# pH-meter.net
KiCad netlist of a schematic drawn in Altium Designer
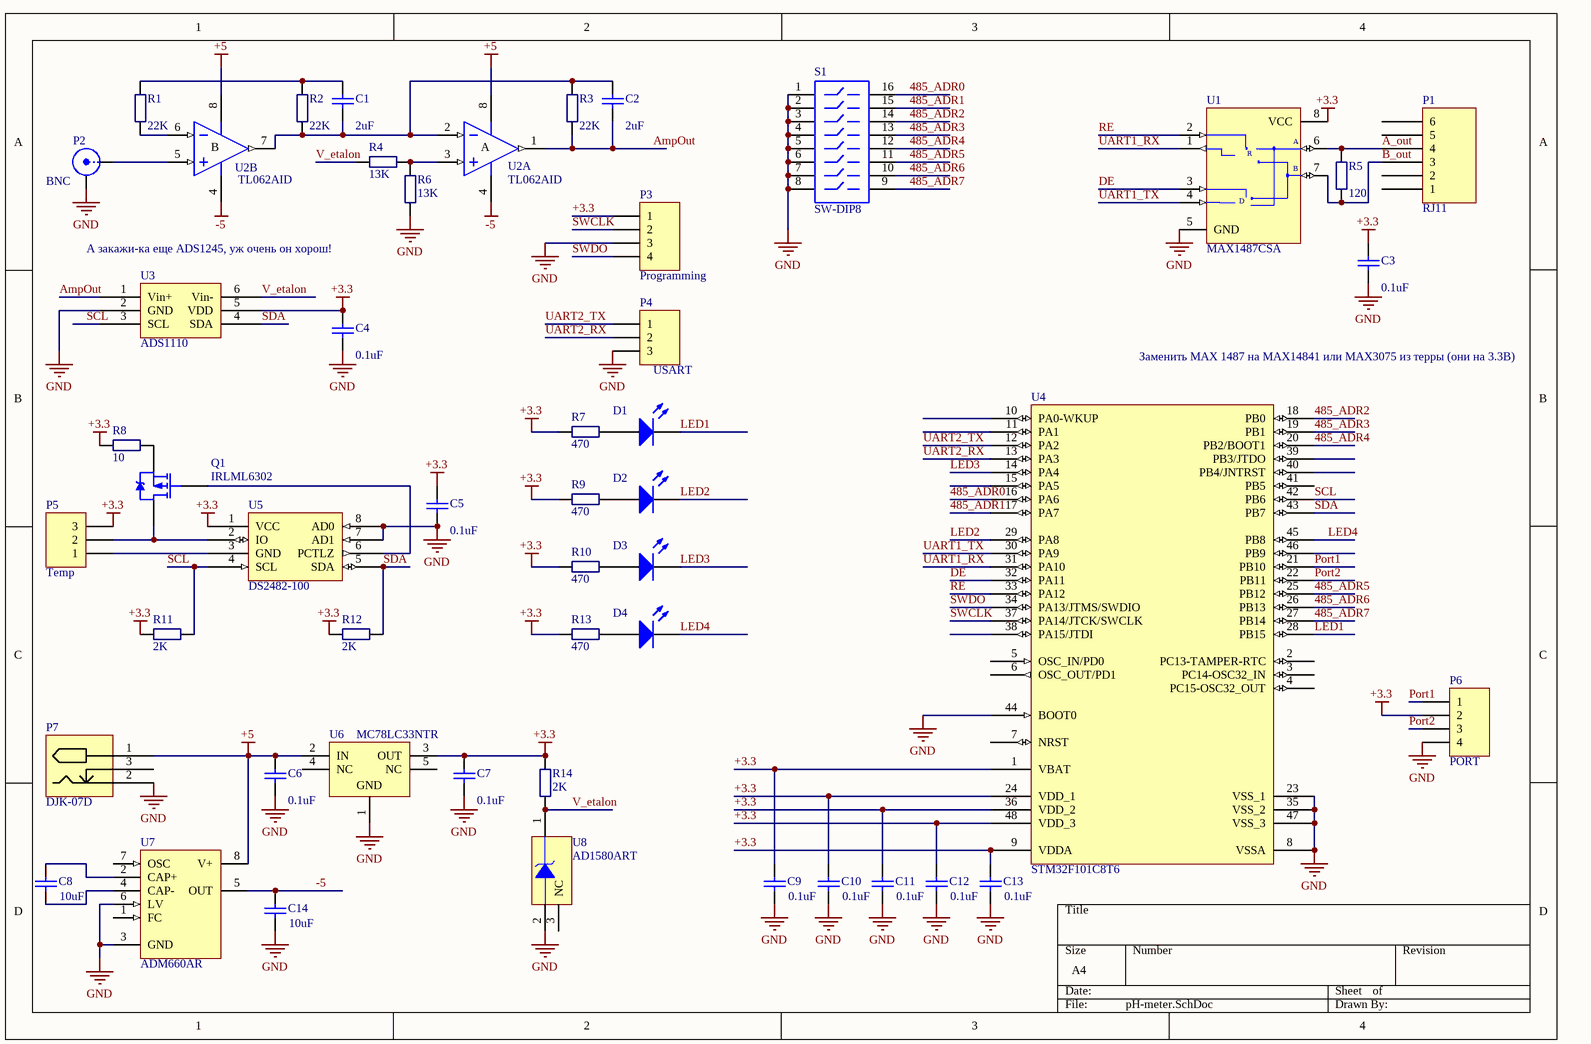
[diagram p0: pH-meter.SchDoc]

(export (version "E")
  (design (tool "Eeschema 10.0.6"))
  (components
    (comp (ref "C1")
      (value "2uF")
      (footprint "1608[0603]")
      (description "Capacitor (Semiconductor SIM Model)")
      (fields (field (name "Comment") "Cap Semi") (field (name "PUBLISHER") "Altium Limited"))
      (libsource (lib "Miscellaneous Devices") (part "Cap Semi"))
    )
    (comp (ref "C2")
      (value "2uF")
      (footprint "1608[0603]")
      (description "Capacitor (Semiconductor SIM Model)")
      (fields (field (name "Comment") "Cap Semi") (field (name "PUBLISHER") "Altium Limited"))
      (libsource (lib "Miscellaneous Devices") (part "Cap Semi"))
    )
    (comp (ref "C3")
      (value "0.1uF")
      (footprint "1608[0603]")
      (description "Capacitor (Semiconductor SIM Model)")
      (fields (field (name "Comment") "Cap Semi") (field (name "PUBLISHER") "Altium Limited"))
      (libsource (lib "Miscellaneous Devices") (part "Cap Semi"))
    )
    (comp (ref "C4")
      (value "0.1uF")
      (footprint "1608[0603]")
      (description "Capacitor (Semiconductor SIM Model)")
      (fields (field (name "Comment") "Cap Semi") (field (name "PUBLISHER") "Altium Limited"))
      (libsource (lib "Miscellaneous Devices") (part "Cap Semi"))
    )
    (comp (ref "C5")
      (value "0.1uF")
      (footprint "1608[0603]")
      (description "Capacitor (Semiconductor SIM Model)")
      (fields (field (name "Comment") "Cap Semi") (field (name "PUBLISHER") "Altium Limited"))
      (libsource (lib "Miscellaneous Devices") (part "Cap Semi"))
    )
    (comp (ref "C6")
      (value "0.1uF")
      (footprint "1608[0603]")
      (description "Capacitor (Semiconductor SIM Model)")
      (fields (field (name "Comment") "Cap Semi") (field (name "PUBLISHER") "Altium Limited"))
      (libsource (lib "Miscellaneous Devices") (part "Cap Semi"))
    )
    (comp (ref "C7")
      (value "0.1uF")
      (footprint "1608[0603]")
      (description "Capacitor (Semiconductor SIM Model)")
      (fields (field (name "Comment") "Cap Semi") (field (name "PUBLISHER") "Altium Limited"))
      (libsource (lib "Miscellaneous Devices") (part "Cap Semi"))
    )
    (comp (ref "C8")
      (value "10uF")
      (footprint "1608[0603]")
      (description "Capacitor (Semiconductor SIM Model)")
      (fields (field (name "Comment") "Cap Semi") (field (name "PUBLISHER") "Altium Limited"))
      (libsource (lib "Miscellaneous Devices") (part "Cap Semi"))
    )
    (comp (ref "C9")
      (value "0.1uF")
      (footprint "1608[0603]")
      (description "Capacitor (Semiconductor SIM Model)")
      (fields (field (name "PUBLISHER") "Altium Limited"))
      (libsource (lib "Miscellaneous Devices") (part "Cap Semi"))
    )
    (comp (ref "C10")
      (value "0.1uF")
      (footprint "1608[0603]")
      (description "Capacitor (Semiconductor SIM Model)")
      (fields (field (name "PUBLISHER") "Altium Limited"))
      (libsource (lib "Miscellaneous Devices") (part "Cap Semi"))
    )
    (comp (ref "C11")
      (value "0.1uF")
      (footprint "1608[0603]")
      (description "Capacitor (Semiconductor SIM Model)")
      (fields (field (name "PUBLISHER") "Altium Limited"))
      (libsource (lib "Miscellaneous Devices") (part "Cap Semi"))
    )
    (comp (ref "C12")
      (value "0.1uF")
      (footprint "1608[0603]")
      (description "Capacitor (Semiconductor SIM Model)")
      (fields (field (name "PUBLISHER") "Altium Limited"))
      (libsource (lib "Miscellaneous Devices") (part "Cap Semi"))
    )
    (comp (ref "C13")
      (value "0.1uF")
      (footprint "1608[0603]")
      (description "Capacitor (Semiconductor SIM Model)")
      (fields (field (name "PUBLISHER") "Altium Limited"))
      (libsource (lib "Miscellaneous Devices") (part "Cap Semi"))
    )
    (comp (ref "C14")
      (value "10uF")
      (footprint "1608[0603]")
      (description "Capacitor (Semiconductor SIM Model)")
      (fields (field (name "Comment") "Cap Semi") (field (name "PUBLISHER") "Altium Limited"))
      (libsource (lib "Miscellaneous Devices") (part "Cap Semi"))
    )
    (comp (ref "D1")
      (value "LED1")
      (footprint "LED-1")
      (description "Typical RED GaAs LED")
      (fields (field (name "PUBLISHER") "Altium Limited"))
      (libsource (lib "Miscellaneous Devices") (part "LED1"))
    )
    (comp (ref "D2")
      (value "LED1")
      (footprint "LED-1")
      (description "Typical RED GaAs LED")
      (fields (field (name "PUBLISHER") "Altium Limited"))
      (libsource (lib "Miscellaneous Devices") (part "LED1"))
    )
    (comp (ref "D3")
      (value "LED1")
      (footprint "LED-1")
      (description "Typical RED GaAs LED")
      (fields (field (name "PUBLISHER") "Altium Limited"))
      (libsource (lib "Miscellaneous Devices") (part "LED1"))
    )
    (comp (ref "D4")
      (value "LED1")
      (footprint "LED-1")
      (description "Typical RED GaAs LED")
      (fields (field (name "PUBLISHER") "Altium Limited"))
      (libsource (lib "Miscellaneous Devices") (part "LED1"))
    )
    (comp (ref "P1")
      (value "RJ11")
      (footprint "RJ11_6")
      (description "RJ11 6pin connector")
      (libsource (lib "MyLib") (part "RJ11_6C"))
    )
    (comp (ref "P2")
      (value "BNC")
      (footprint "BNC_RA CON")
      (description "BNC Elbow Connector")
      (fields (field (name "PUBLISHER") "Altium Limited"))
      (libsource (lib "Miscellaneous Connectors") (part "BNC"))
    )
    (comp (ref "P3")
      (value "Programming")
      (footprint "HDR1X4")
      (description "Header, 4-Pin")
      (fields (field (name "PUBLISHER") "Altium Limited"))
      (libsource (lib "Miscellaneous Connectors") (part "Header 4"))
    )
    (comp (ref "P4")
      (value "USART")
      (footprint "HDR1X3")
      (description "Header, 3-Pin")
      (fields (field (name "PUBLISHER") "Altium Limited"))
      (libsource (lib "Miscellaneous Connectors") (part "Header 3"))
    )
    (comp (ref "P5")
      (value "Temp")
      (footprint "HDR1X3")
      (description "Header, 3-Pin")
      (fields (field (name "PUBLISHER") "Altium Limited"))
      (libsource (lib "") (part "Header 3_1"))
    )
    (comp (ref "P6")
      (value "PORT")
      (footprint "HDR1X4")
      (description "Header, 4-Pin")
      (fields (field (name "PUBLISHER") "Altium Limited"))
      (libsource (lib "Miscellaneous Connectors") (part "Header 4"))
    )
    (comp (ref "P7")
      (value "DJK-07D")
      (footprint "DJK-07D")
      (description "DJK-07D Разъем питани  штырев. 1,3мм (п) на плату")
      (libsource (lib "MyLib") (part "DJK-07D"))
    )
    (comp (ref "Q1")
      (value "IRLML6302")
      (footprint "SOT-23_N")
      (description "HEXFET Power MOSFET")
      (fields (field (name "PUBLISHER") "Altium Limited"))
      (libsource (lib "IR Discrete MOSFET - Power") (part "IRLML6302"))
    )
    (comp (ref "R1")
      (value "22K")
      (footprint "J1-0603")
      (description "Resistor")
      (fields (field (name "Comment") "Res_SMD") (field (name "PUBLISHER") "Altium Limited"))
      (libsource (lib "MyLib") (part "Res_SMD"))
    )
    (comp (ref "R2")
      (value "22K")
      (footprint "J1-0603")
      (description "Resistor")
      (fields (field (name "Comment") "Res_SMD") (field (name "PUBLISHER") "Altium Limited"))
      (libsource (lib "MyLib") (part "Res_SMD"))
    )
    (comp (ref "R3")
      (value "22K")
      (footprint "J1-0603")
      (description "Resistor")
      (fields (field (name "Comment") "Res_SMD") (field (name "PUBLISHER") "Altium Limited"))
      (libsource (lib "MyLib") (part "Res_SMD"))
    )
    (comp (ref "R4")
      (value "13K")
      (footprint "J1-0603")
      (description "Resistor")
      (fields (field (name "Comment") "Res_SMD") (field (name "PUBLISHER") "Altium Limited"))
      (libsource (lib "MyLib") (part "Res_SMD"))
    )
    (comp (ref "R5")
      (value "120")
      (footprint "J1-0603")
      (description "Resistor")
      (fields (field (name "Comment") "Res_SMD") (field (name "PUBLISHER") "Altium Limited"))
      (libsource (lib "MyLib") (part "Res_SMD"))
    )
    (comp (ref "R6")
      (value "13K")
      (footprint "J1-0603")
      (description "Resistor")
      (fields (field (name "Comment") "Res_SMD") (field (name "PUBLISHER") "Altium Limited"))
      (libsource (lib "MyLib") (part "Res_SMD"))
    )
    (comp (ref "R7")
      (value "470")
      (footprint "J1-0603")
      (description "Resistor")
      (fields (field (name "PUBLISHER") "Altium Limited"))
      (libsource (lib "MyLib") (part "Res_SMD"))
    )
    (comp (ref "R8")
      (value "10")
      (footprint "J1-0603")
      (description "Resistor")
      (fields (field (name "Comment") "Res_SMD") (field (name "PUBLISHER") "Altium Limited"))
      (libsource (lib "MyLib") (part "Res_SMD"))
    )
    (comp (ref "R9")
      (value "470")
      (footprint "J1-0603")
      (description "Resistor")
      (fields (field (name "PUBLISHER") "Altium Limited"))
      (libsource (lib "MyLib") (part "Res_SMD"))
    )
    (comp (ref "R10")
      (value "470")
      (footprint "J1-0603")
      (description "Resistor")
      (fields (field (name "PUBLISHER") "Altium Limited"))
      (libsource (lib "MyLib") (part "Res_SMD"))
    )
    (comp (ref "R11")
      (value "2K")
      (footprint "J1-0603")
      (description "Resistor")
      (fields (field (name "Comment") "Res_SMD") (field (name "PUBLISHER") "Altium Limited"))
      (libsource (lib "MyLib") (part "Res_SMD"))
    )
    (comp (ref "R12")
      (value "2K")
      (footprint "J1-0603")
      (description "Resistor")
      (fields (field (name "Comment") "Res_SMD") (field (name "PUBLISHER") "Altium Limited"))
      (libsource (lib "MyLib") (part "Res_SMD"))
    )
    (comp (ref "R13")
      (value "470")
      (footprint "J1-0603")
      (description "Resistor")
      (fields (field (name "PUBLISHER") "Altium Limited"))
      (libsource (lib "MyLib") (part "Res_SMD"))
    )
    (comp (ref "R14")
      (value "2K")
      (footprint "J1-0603")
      (description "Resistor")
      (fields (field (name "Comment") "Res_SMD") (field (name "PUBLISHER") "Altium Limited"))
      (libsource (lib "MyLib") (part "Res_SMD"))
    )
    (comp (ref "S1")
      (value "SW-DIP8")
      (footprint "DIP-16-KEY")
      (description "4009 Series DIP Switch, Raised actuator")
      (fields (field (name "PUBLISHER") "Altium Limited"))
      (libsource (lib "Miscellaneous Devices") (part "SW-DIP8"))
    )
    (comp (ref "U1")
      (value "MAX1487CSA")
      (footprint "NSO8_N")
      (description "Low-Power, Slew-Rate-Limited RS-485/RS-422 Transceiver")
      (fields (field (name "PUBLISHER") "Altium Limited"))
      (libsource (lib "Maxim Communication Transceiver") (part "MAX1487CSA"))
    )
    (comp (ref "U2")
      (value "TL062AID")
      (footprint "SO8_N")
      (description "Low-Power J-FET Dual Bipolar Operational Amplifier")
      (fields (field (name "PUBLISHER") "Altium Limited"))
      (libsource (lib "ST Operational Amplifier") (part "TL062AID"))
    )
    (comp (ref "U3")
      (value "ADS1110")
      (footprint "SOT-23_A")
      (description "16-Bit ANALOG-TO-DIGITAL CONVERTER")
      (libsource (lib "MyLib") (part "ADS1110"))
    )
    (comp (ref "U4")
      (value "STM32F101C8T6")
      (footprint "LQFP48_N")
      (description "STM32 ARM-based 32-bit MCU with 64 Kbytes Flash, 48-pin LQFP, Industrial Temperature")
      (fields (field (name "PUBLISHER") "Altium Limited"))
      (libsource (lib "ST Microcontroller 32-Bit STM32") (part "STM32F101C8T6"))
    )
    (comp (ref "U5")
      (value "DS2482-100")
      (footprint "NSO8_L")
      (description "Single-Channel 1-Wire Master")
      (libsource (lib "MyLib") (part "DS2482-100"))
    )
    (comp (ref "U6")
      (value "MC78LC33NTR")
      (footprint "1212-01")
      (description "Micropower Voltage Regulator")
      (fields (field (name "PUBLISHER") "Altium Limited"))
      (libsource (lib "ON Semi Power Mgt Voltage Regulator") (part "MC78LC33NTR"))
    )
    (comp (ref "U7")
      (value "ADM660AR")
      (footprint "SO-8_N")
      (description "CMOS Switched-Capacitor Voltage Converter")
      (fields (field (name "PUBLISHER") "Altium Limited"))
      (libsource (lib "AD Power Mgt Charge Pump") (part "ADM660AR"))
    )
    (comp (ref "U8")
      (value "AD1580ART")
      (footprint "RT-3_N")
      (description "1.2V Micropower, Precision Shunt Voltage Reference")
      (fields (field (name "PUBLISHER") "Altium Limited"))
      (libsource (lib "AD Power Mgt Voltage Reference") (part "AD1580ART"))
    )
  )
  (nets
    (net (code "1") (name "+3.3") (class "Default")
      (node (ref "C10") (pin "2") (pinfunction "2_2") (pintype "passive"))
      (node (ref "C11") (pin "2") (pinfunction "2_2") (pintype "passive"))
      (node (ref "C12") (pin "2") (pinfunction "2_2") (pintype "passive"))
      (node (ref "C13") (pin "2") (pinfunction "2_2") (pintype "passive"))
      (node (ref "C3") (pin "2") (pinfunction "2_2") (pintype "passive"))
      (node (ref "C4") (pin "2") (pinfunction "2_2") (pintype "passive"))
      (node (ref "C5") (pin "2") (pinfunction "2_2") (pintype "passive"))
      (node (ref "C7") (pin "2") (pinfunction "2_2") (pintype "passive"))
      (node (ref "C9") (pin "2") (pinfunction "2_2") (pintype "passive"))
      (node (ref "P3") (pin "1") (pinfunction "1_1") (pintype "passive"))
      (node (ref "P5") (pin "3") (pinfunction "3_3") (pintype "passive"))
      (node (ref "P6") (pin "2") (pinfunction "2_2") (pintype "passive"))
      (node (ref "R10") (pin "2") (pinfunction "2_2") (pintype "passive"))
      (node (ref "R11") (pin "2") (pinfunction "2_2") (pintype "passive"))
      (node (ref "R12") (pin "2") (pinfunction "2_2") (pintype "passive"))
      (node (ref "R13") (pin "2") (pinfunction "2_2") (pintype "passive"))
      (node (ref "R14") (pin "2") (pinfunction "2_2") (pintype "passive"))
      (node (ref "R7") (pin "2") (pinfunction "2_2") (pintype "passive"))
      (node (ref "R8") (pin "1") (pinfunction "1_1") (pintype "passive"))
      (node (ref "R9") (pin "2") (pinfunction "2_2") (pintype "passive"))
      (node (ref "U1") (pin "8") (pinfunction "VCC_8") (pintype "power_in"))
      (node (ref "U3") (pin "5") (pinfunction "VDD_5") (pintype "passive"))
      (node (ref "U4") (pin "1") (pinfunction "VBAT_1") (pintype "power_in"))
      (node (ref "U4") (pin "24") (pinfunction "VDD_1_24") (pintype "power_in"))
      (node (ref "U4") (pin "36") (pinfunction "VDD_2_36") (pintype "power_in"))
      (node (ref "U4") (pin "48") (pinfunction "VDD_3_48") (pintype "power_in"))
      (node (ref "U4") (pin "9") (pinfunction "VDDA_9") (pintype "power_in"))
      (node (ref "U5") (pin "1") (pinfunction "VCC_1") (pintype "power_in"))
      (node (ref "U6") (pin "3") (pinfunction "OUT_3") (pintype "power_in"))
    )
    (net (code "2") (name "+5") (class "Default")
      (node (ref "C6") (pin "2") (pinfunction "2_2") (pintype "passive"))
      (node (ref "P7") (pin "1") (pintype "passive"))
      (node (ref "U2") (pin "8") (pinfunction "V+_8") (pintype "power_in"))
      (node (ref "U6") (pin "2") (pinfunction "IN_2") (pintype "power_in"))
      (node (ref "U7") (pin "8") (pinfunction "V+_8") (pintype "power_in"))
    )
    (net (code "3") (name "-5") (class "Default")
      (node (ref "C14") (pin "2") (pinfunction "2_2") (pintype "passive"))
      (node (ref "U2") (pin "4") (pinfunction "V-_4") (pintype "power_in"))
      (node (ref "U7") (pin "5") (pinfunction "OUT_5") (pintype "power_in"))
    )
    (net (code "4") (name "/485_ADR0") (class "Default")
      (node (ref "S1") (pin "16") (pinfunction "16_16") (pintype "passive"))
      (node (ref "U4") (pin "16") (pinfunction "PA6_16") (pintype "bidirectional"))
    )
    (net (code "5") (name "/485_ADR1") (class "Default")
      (node (ref "S1") (pin "15") (pinfunction "15_15") (pintype "passive"))
      (node (ref "U4") (pin "17") (pinfunction "PA7_17") (pintype "bidirectional"))
    )
    (net (code "6") (name "/485_ADR2") (class "Default")
      (node (ref "S1") (pin "14") (pinfunction "14_14") (pintype "passive"))
      (node (ref "U4") (pin "18") (pinfunction "PB0_18") (pintype "bidirectional"))
    )
    (net (code "7") (name "/485_ADR3") (class "Default")
      (node (ref "S1") (pin "13") (pinfunction "13_13") (pintype "passive"))
      (node (ref "U4") (pin "19") (pinfunction "PB1_19") (pintype "bidirectional"))
    )
    (net (code "8") (name "/485_ADR4") (class "Default")
      (node (ref "S1") (pin "12") (pinfunction "12_12") (pintype "passive"))
      (node (ref "U4") (pin "20") (pinfunction "PB2/BOOT1_20") (pintype "bidirectional"))
    )
    (net (code "9") (name "/485_ADR5") (class "Default")
      (node (ref "S1") (pin "11") (pinfunction "11_11") (pintype "passive"))
      (node (ref "U4") (pin "25") (pinfunction "PB12_25") (pintype "bidirectional"))
    )
    (net (code "10") (name "/485_ADR6") (class "Default")
      (node (ref "S1") (pin "10") (pinfunction "10_10") (pintype "passive"))
      (node (ref "U4") (pin "26") (pinfunction "PB13_26") (pintype "bidirectional"))
    )
    (net (code "11") (name "/485_ADR7") (class "Default")
      (node (ref "S1") (pin "9") (pinfunction "9_9") (pintype "passive"))
      (node (ref "U4") (pin "27") (pinfunction "PB14_27") (pintype "bidirectional"))
    )
    (net (code "12") (name "/A_out") (class "Default")
      (node (ref "P1") (pin "4") (pinfunction "4_4") (pintype "passive"))
      (node (ref "R5") (pin "1") (pinfunction "1_1") (pintype "passive"))
      (node (ref "U1") (pin "6") (pinfunction "A_6") (pintype "bidirectional"))
    )
    (net (code "13") (name "/AmpOut") (class "Default")
      (node (ref "C2") (pin "1") (pinfunction "1_1") (pintype "passive"))
      (node (ref "R3") (pin "2") (pinfunction "2_2") (pintype "passive"))
      (node (ref "U2") (pin "1") (pinfunction "OUT_1") (pintype "output"))
      (node (ref "U3") (pin "1") (pinfunction "Vin+_1") (pintype "passive"))
    )
    (net (code "14") (name "/B_out") (class "Default")
      (node (ref "P1") (pin "3") (pinfunction "3_3") (pintype "passive"))
      (node (ref "R5") (pin "2") (pinfunction "2_2") (pintype "passive"))
      (node (ref "U1") (pin "7") (pinfunction "B_7") (pintype "bidirectional"))
    )
    (net (code "15") (name "/DE") (class "Default")
      (node (ref "U1") (pin "3") (pinfunction "DE_3") (pintype "input"))
      (node (ref "U4") (pin "32") (pinfunction "PA11_32") (pintype "bidirectional"))
    )
    (net (code "16") (name "/LED1") (class "Default")
      (node (ref "D1") (pin "2") (pinfunction "K_2") (pintype "passive"))
      (node (ref "U4") (pin "28") (pinfunction "PB15_28") (pintype "bidirectional"))
    )
    (net (code "17") (name "/LED2") (class "Default")
      (node (ref "D2") (pin "2") (pinfunction "K_2") (pintype "passive"))
      (node (ref "U4") (pin "29") (pinfunction "PA8_29") (pintype "bidirectional"))
    )
    (net (code "18") (name "/LED3") (class "Default")
      (node (ref "D3") (pin "2") (pinfunction "K_2") (pintype "passive"))
      (node (ref "U4") (pin "14") (pinfunction "PA4_14") (pintype "bidirectional"))
    )
    (net (code "19") (name "/LED4") (class "Default")
      (node (ref "D4") (pin "2") (pinfunction "K_2") (pintype "passive"))
      (node (ref "U4") (pin "45") (pinfunction "PB8_45") (pintype "bidirectional"))
    )
    (net (code "20") (name "/Port1") (class "Default")
      (node (ref "P6") (pin "1") (pinfunction "1_1") (pintype "passive"))
      (node (ref "U4") (pin "21") (pinfunction "PB10_21") (pintype "bidirectional"))
    )
    (net (code "21") (name "/Port2") (class "Default")
      (node (ref "P6") (pin "3") (pinfunction "3_3") (pintype "passive"))
      (node (ref "U4") (pin "22") (pinfunction "PB11_22") (pintype "bidirectional"))
    )
    (net (code "22") (name "/RE") (class "Default")
      (node (ref "U1") (pin "2") (pinfunction "~{RE}_2") (pintype "input"))
      (node (ref "U4") (pin "33") (pinfunction "PA12_33") (pintype "bidirectional"))
    )
    (net (code "23") (name "/SCL") (class "Default")
      (node (ref "R11") (pin "1") (pinfunction "1_1") (pintype "passive"))
      (node (ref "U3") (pin "3") (pinfunction "SCL_3") (pintype "passive"))
      (node (ref "U4") (pin "42") (pinfunction "PB6_42") (pintype "bidirectional"))
      (node (ref "U5") (pin "4") (pinfunction "SCL_4") (pintype "input"))
    )
    (net (code "24") (name "/SDA") (class "Default")
      (node (ref "R12") (pin "1") (pinfunction "1_1") (pintype "passive"))
      (node (ref "U3") (pin "4") (pinfunction "SDA_4") (pintype "passive"))
      (node (ref "U4") (pin "43") (pinfunction "PB7_43") (pintype "bidirectional"))
      (node (ref "U5") (pin "5") (pinfunction "SDA_5") (pintype "bidirectional"))
    )
    (net (code "25") (name "/SWCLK") (class "Default")
      (node (ref "P3") (pin "2") (pinfunction "2_2") (pintype "passive"))
      (node (ref "U4") (pin "37") (pinfunction "PA14/JTCK/SWCLK_37") (pintype "bidirectional"))
    )
    (net (code "26") (name "/SWDO") (class "Default")
      (node (ref "P3") (pin "4") (pinfunction "4_4") (pintype "passive"))
      (node (ref "U4") (pin "34") (pinfunction "PA13/JTMS/SWDIO_34") (pintype "bidirectional"))
    )
    (net (code "27") (name "/UART1_RX") (class "Default")
      (node (ref "U1") (pin "1") (pinfunction "RO_1") (pintype "output"))
      (node (ref "U4") (pin "31") (pinfunction "PA10_31") (pintype "bidirectional"))
    )
    (net (code "28") (name "/UART1_TX") (class "Default")
      (node (ref "U1") (pin "4") (pinfunction "DI_4") (pintype "input"))
      (node (ref "U4") (pin "30") (pinfunction "PA9_30") (pintype "bidirectional"))
    )
    (net (code "29") (name "/UART2_RX") (class "Default")
      (node (ref "P4") (pin "2") (pinfunction "2_2") (pintype "passive"))
      (node (ref "U4") (pin "13") (pinfunction "PA3_13") (pintype "bidirectional"))
    )
    (net (code "30") (name "/UART2_TX") (class "Default")
      (node (ref "P4") (pin "1") (pinfunction "1_1") (pintype "passive"))
      (node (ref "U4") (pin "12") (pinfunction "PA2_12") (pintype "bidirectional"))
    )
    (net (code "31") (name "/V_etalon") (class "Default")
      (node (ref "R14") (pin "1") (pinfunction "1_1") (pintype "passive"))
      (node (ref "R4") (pin "1") (pinfunction "1_1") (pintype "passive"))
      (node (ref "U3") (pin "6") (pinfunction "Vin-_6") (pintype "passive"))
      (node (ref "U8") (pin "1") (pinfunction "V+_1") (pintype "power_in"))
    )
    (net (code "32") (name "GND") (class "Default")
      (node (ref "C10") (pin "1") (pinfunction "1_1") (pintype "passive"))
      (node (ref "C11") (pin "1") (pinfunction "1_1") (pintype "passive"))
      (node (ref "C12") (pin "1") (pinfunction "1_1") (pintype "passive"))
      (node (ref "C13") (pin "1") (pinfunction "1_1") (pintype "passive"))
      (node (ref "C14") (pin "1") (pinfunction "1_1") (pintype "passive"))
      (node (ref "C3") (pin "1") (pinfunction "1_1") (pintype "passive"))
      (node (ref "C4") (pin "1") (pinfunction "1_1") (pintype "passive"))
      (node (ref "C5") (pin "1") (pinfunction "1_1") (pintype "passive"))
      (node (ref "C6") (pin "1") (pinfunction "1_1") (pintype "passive"))
      (node (ref "C7") (pin "1") (pinfunction "1_1") (pintype "passive"))
      (node (ref "C9") (pin "1") (pinfunction "1_1") (pintype "passive"))
      (node (ref "P2") (pin "2") (pinfunction "Y_2") (pintype "passive"))
      (node (ref "P3") (pin "3") (pinfunction "3_3") (pintype "passive"))
      (node (ref "P4") (pin "3") (pinfunction "3_3") (pintype "passive"))
      (node (ref "P6") (pin "4") (pinfunction "4_4") (pintype "passive"))
      (node (ref "P7") (pin "2") (pintype "passive"))
      (node (ref "R6") (pin "1") (pinfunction "1_1") (pintype "passive"))
      (node (ref "S1") (pin "1") (pinfunction "1_1") (pintype "passive"))
      (node (ref "S1") (pin "2") (pinfunction "2_2") (pintype "passive"))
      (node (ref "S1") (pin "3") (pinfunction "3_3") (pintype "passive"))
      (node (ref "S1") (pin "4") (pinfunction "4_4") (pintype "passive"))
      (node (ref "S1") (pin "5") (pinfunction "5_5") (pintype "passive"))
      (node (ref "S1") (pin "6") (pinfunction "6_6") (pintype "passive"))
      (node (ref "S1") (pin "7") (pinfunction "7_7") (pintype "passive"))
      (node (ref "S1") (pin "8") (pinfunction "8_8") (pintype "passive"))
      (node (ref "U1") (pin "5") (pinfunction "GND_5") (pintype "power_in"))
      (node (ref "U3") (pin "2") (pinfunction "GND_2") (pintype "passive"))
      (node (ref "U4") (pin "23") (pinfunction "VSS_1_23") (pintype "power_in"))
      (node (ref "U4") (pin "35") (pinfunction "VSS_2_35") (pintype "power_in"))
      (node (ref "U4") (pin "44") (pinfunction "BOOT0_44") (pintype "input"))
      (node (ref "U4") (pin "47") (pinfunction "VSS_3_47") (pintype "power_in"))
      (node (ref "U4") (pin "8") (pinfunction "VSSA_8") (pintype "power_in"))
      (node (ref "U5") (pin "7") (pinfunction "AD1_7") (pintype "input"))
      (node (ref "U5") (pin "8") (pinfunction "AD0_8") (pintype "input"))
      (node (ref "U6") (pin "1") (pinfunction "GND_1") (pintype "power_in"))
      (node (ref "U7") (pin "3") (pinfunction "GND_3") (pintype "power_in"))
      (node (ref "U7") (pin "6") (pinfunction "LV_6") (pintype "input"))
      (node (ref "U8") (pin "2") (pinfunction "V-_2") (pintype "power_in"))
    )
    (net (code "33") (name "Net-(C1-Pad2)") (class "Default")
      (node (ref "C1") (pin "2") (pinfunction "2_2") (pintype "passive"))
      (node (ref "R1") (pin "1") (pinfunction "1_1") (pintype "passive"))
      (node (ref "R2") (pin "1") (pinfunction "1_1") (pintype "passive"))
    )
    (net (code "34") (name "Net-(D1-A)") (class "Default")
      (node (ref "D1") (pin "1") (pinfunction "A_1") (pintype "passive"))
      (node (ref "R7") (pin "1") (pinfunction "1_1") (pintype "passive"))
    )
    (net (code "35") (name "Net-(D2-A)") (class "Default")
      (node (ref "D2") (pin "1") (pinfunction "A_1") (pintype "passive"))
      (node (ref "R9") (pin "1") (pinfunction "1_1") (pintype "passive"))
    )
    (net (code "36") (name "Net-(D3-A)") (class "Default")
      (node (ref "D3") (pin "1") (pinfunction "A_1") (pintype "passive"))
      (node (ref "R10") (pin "1") (pinfunction "1_1") (pintype "passive"))
    )
    (net (code "37") (name "Net-(D4-A)") (class "Default")
      (node (ref "D4") (pin "1") (pinfunction "A_1") (pintype "passive"))
      (node (ref "R13") (pin "1") (pinfunction "1_1") (pintype "passive"))
    )
    (net (code "38") (name "Net-(P2-X)") (class "Default")
      (node (ref "P2") (pin "1") (pinfunction "X_1") (pintype "passive"))
      (node (ref "U2") (pin "5") (pinfunction "IN+_5") (pintype "input"))
    )
    (net (code "39") (name "Net-(Q1-D)") (class "Default")
      (node (ref "P5") (pin "2") (pinfunction "2_2") (pintype "passive"))
      (node (ref "Q1") (pin "3") (pinfunction "D_3") (pintype "passive"))
      (node (ref "U5") (pin "2") (pinfunction "IO_2") (pintype "bidirectional"))
    )
    (net (code "40") (name "Net-(Q1-G)") (class "Default")
      (node (ref "Q1") (pin "1") (pinfunction "G_1") (pintype "passive"))
      (node (ref "U5") (pin "6") (pinfunction "PCTLZ_6") (pintype "output"))
    )
    (net (code "41") (name "Net-(Q1-S)") (class "Default")
      (node (ref "Q1") (pin "2") (pinfunction "S_2") (pintype "passive"))
      (node (ref "R8") (pin "2") (pinfunction "2_2") (pintype "passive"))
    )
    (net (code "42") (name "Net-(U2A-IN+)") (class "Default")
      (node (ref "R4") (pin "2") (pinfunction "2_2") (pintype "passive"))
      (node (ref "R6") (pin "2") (pinfunction "2_2") (pintype "passive"))
      (node (ref "U2") (pin "3") (pinfunction "IN+_3") (pintype "input"))
    )
    (net (code "43") (name "Net-(U2A-IN-)") (class "Default")
      (node (ref "C1") (pin "1") (pinfunction "1_1") (pintype "passive"))
      (node (ref "C2") (pin "2") (pinfunction "2_2") (pintype "passive"))
      (node (ref "R2") (pin "2") (pinfunction "2_2") (pintype "passive"))
      (node (ref "R3") (pin "1") (pinfunction "1_1") (pintype "passive"))
      (node (ref "U2") (pin "2") (pinfunction "IN-_2") (pintype "input"))
      (node (ref "U2") (pin "7") (pinfunction "OUT_7") (pintype "output"))
    )
    (net (code "44") (name "Net-(U2B-IN-)") (class "Default")
      (node (ref "R1") (pin "2") (pinfunction "2_2") (pintype "passive"))
      (node (ref "U2") (pin "6") (pinfunction "IN-_6") (pintype "input"))
    )
    (net (code "45") (name "Net-(U5-GND)") (class "Default")
      (node (ref "P5") (pin "1") (pinfunction "1_1") (pintype "passive"))
      (node (ref "U5") (pin "3") (pinfunction "GND_3") (pintype "power_in"))
    )
    (net (code "46") (name "Net-(U7-CAP+)") (class "Default")
      (node (ref "C8") (pin "2") (pinfunction "2_2") (pintype "passive"))
      (node (ref "U7") (pin "2") (pinfunction "CAP+_2") (pintype "passive"))
    )
    (net (code "47") (name "Net-(U7-CAP-)") (class "Default")
      (node (ref "C8") (pin "1") (pinfunction "1_1") (pintype "passive"))
      (node (ref "U7") (pin "4") (pinfunction "CAP-_4") (pintype "passive"))
    )
    (net (code "48") (name "unconnected-(P1-Pad1)") (class "Default")
      (node (ref "P1") (pin "1") (pinfunction "1_1") (pintype "passive"))
    )
    (net (code "49") (name "unconnected-(P1-Pad2)") (class "Default")
      (node (ref "P1") (pin "2") (pinfunction "2_2") (pintype "passive"))
    )
    (net (code "50") (name "unconnected-(P1-Pad5)") (class "Default")
      (node (ref "P1") (pin "5") (pinfunction "5_5") (pintype "passive"))
    )
    (net (code "51") (name "unconnected-(P1-Pad6)") (class "Default")
      (node (ref "P1") (pin "6") (pinfunction "6_6") (pintype "passive"))
    )
    (net (code "52") (name "unconnected-(P7-Pad3)") (class "Default")
      (node (ref "P7") (pin "3") (pintype "passive"))
    )
    (net (code "53") (name "unconnected-(U4-NRST-Pad7)") (class "Default")
      (node (ref "U4") (pin "7") (pinfunction "NRST_7") (pintype "bidirectional"))
    )
    (net (code "54") (name "unconnected-(U4-OSC_IN{slash}PD0-Pad5)") (class "Default")
      (node (ref "U4") (pin "5") (pinfunction "OSC_IN/PD0_5") (pintype "input"))
    )
    (net (code "55") (name "unconnected-(U4-OSC_OUT{slash}PD1-Pad6)") (class "Default")
      (node (ref "U4") (pin "6") (pinfunction "OSC_OUT/PD1_6") (pintype "output"))
    )
    (net (code "56") (name "unconnected-(U4-PA0-WKUP-Pad10)") (class "Default")
      (node (ref "U4") (pin "10") (pinfunction "PA0-WKUP_10") (pintype "bidirectional"))
    )
    (net (code "57") (name "unconnected-(U4-PA1-Pad11)") (class "Default")
      (node (ref "U4") (pin "11") (pinfunction "PA1_11") (pintype "bidirectional"))
    )
    (net (code "58") (name "unconnected-(U4-PA5-Pad15)") (class "Default")
      (node (ref "U4") (pin "15") (pinfunction "PA5_15") (pintype "bidirectional"))
    )
    (net (code "59") (name "unconnected-(U4-PA15{slash}JTDI-Pad38)") (class "Default")
      (node (ref "U4") (pin "38") (pinfunction "PA15/JTDI_38") (pintype "bidirectional"))
    )
    (net (code "60") (name "unconnected-(U4-PB3{slash}JTDO-Pad39)") (class "Default")
      (node (ref "U4") (pin "39") (pinfunction "PB3/JTDO_39") (pintype "bidirectional"))
    )
    (net (code "61") (name "unconnected-(U4-PB4{slash}JNTRST-Pad40)") (class "Default")
      (node (ref "U4") (pin "40") (pinfunction "PB4/JNTRST_40") (pintype "bidirectional"))
    )
    (net (code "62") (name "unconnected-(U4-PB5-Pad41)") (class "Default")
      (node (ref "U4") (pin "41") (pinfunction "PB5_41") (pintype "bidirectional"))
    )
    (net (code "63") (name "unconnected-(U4-PB9-Pad46)") (class "Default")
      (node (ref "U4") (pin "46") (pinfunction "PB9_46") (pintype "bidirectional"))
    )
    (net (code "64") (name "unconnected-(U4-PC13-TAMPER-RTC-Pad2)") (class "Default")
      (node (ref "U4") (pin "2") (pinfunction "PC13-TAMPER-RTC_2") (pintype "bidirectional"))
    )
    (net (code "65") (name "unconnected-(U4-PC14-OSC32_IN-Pad3)") (class "Default")
      (node (ref "U4") (pin "3") (pinfunction "PC14-OSC32_IN_3") (pintype "bidirectional"))
    )
    (net (code "66") (name "unconnected-(U4-PC15-OSC32_OUT-Pad4)") (class "Default")
      (node (ref "U4") (pin "4") (pinfunction "PC15-OSC32_OUT_4") (pintype "bidirectional"))
    )
    (net (code "67") (name "unconnected-(U6-NC-Pad4)") (class "Default")
      (node (ref "U6") (pin "4") (pinfunction "NC_4") (pintype "passive"))
    )
    (net (code "68") (name "unconnected-(U6-NC-Pad5)") (class "Default")
      (node (ref "U6") (pin "5") (pinfunction "NC_5") (pintype "passive"))
    )
    (net (code "69") (name "unconnected-(U7-FC-Pad1)") (class "Default")
      (node (ref "U7") (pin "1") (pinfunction "FC_1") (pintype "input"))
    )
    (net (code "70") (name "unconnected-(U7-OSC-Pad7)") (class "Default")
      (node (ref "U7") (pin "7") (pinfunction "OSC_7") (pintype "input"))
    )
    (net (code "71") (name "unconnected-(U8-NC-Pad3)") (class "Default")
      (node (ref "U8") (pin "3") (pinfunction "NC_3") (pintype "passive"))
    )
  )
)
